# audio_switch.net
KiCad netlist of a schematic drawn in EAGLE
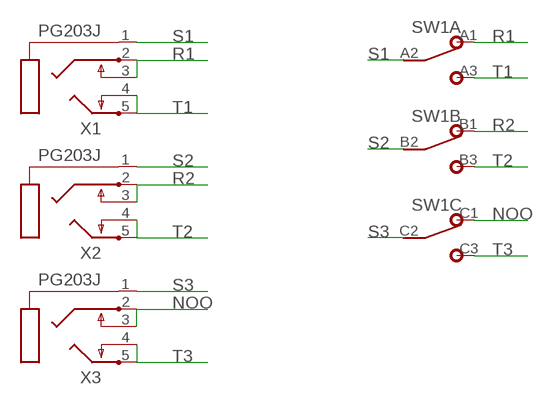
[diagram p0: schematic, sheet 1]

(export (version "E")
  (design (tool "Eeschema 10.0.6"))
  (components
    (comp (ref "SW1")
      (value "3PDT")
      (footprint "eagle-import:3PDT")
      (libsource (lib "eagle-import") (part "3PDT"))
    )
    (comp (ref "X1")
      (value "PG203J")
      (footprint "eagle-import:PG203J")
      (libsource (lib "eagle-import") (part "PG203J"))
    )
    (comp (ref "X2")
      (value "PG203J")
      (footprint "eagle-import:PG203J")
      (libsource (lib "eagle-import") (part "PG203J"))
    )
    (comp (ref "X3")
      (value "PG203J")
      (footprint "eagle-import:PG203J")
      (libsource (lib "eagle-import") (part "PG203J"))
    )
  )
  (nets
    (net (code "1") (name "/NOO") (class "Default")
      (node (ref "SW1") (pin "C1") (pinfunction "1_C1") (pintype "passive"))
      (node (ref "X3") (pin "2") (pinfunction "2_2") (pintype "passive"))
      (node (ref "X3") (pin "3") (pinfunction "3_3") (pintype "passive"))
    )
    (net (code "2") (name "/R1") (class "Default")
      (node (ref "SW1") (pin "A1") (pinfunction "1_A1") (pintype "passive"))
      (node (ref "X1") (pin "2") (pinfunction "2_2") (pintype "passive"))
      (node (ref "X1") (pin "3") (pinfunction "3_3") (pintype "passive"))
    )
    (net (code "3") (name "/R2") (class "Default")
      (node (ref "SW1") (pin "B1") (pinfunction "1_B1") (pintype "passive"))
      (node (ref "X2") (pin "2") (pinfunction "2_2") (pintype "passive"))
      (node (ref "X2") (pin "3") (pinfunction "3_3") (pintype "passive"))
    )
    (net (code "4") (name "/S1") (class "Default")
      (node (ref "SW1") (pin "A2") (pinfunction "2_A2") (pintype "passive"))
      (node (ref "X1") (pin "1") (pinfunction "1_1") (pintype "passive"))
    )
    (net (code "5") (name "/S2") (class "Default")
      (node (ref "SW1") (pin "B2") (pinfunction "2_B2") (pintype "passive"))
      (node (ref "X2") (pin "1") (pinfunction "1_1") (pintype "passive"))
    )
    (net (code "6") (name "/S3") (class "Default")
      (node (ref "SW1") (pin "C2") (pinfunction "2_C2") (pintype "passive"))
      (node (ref "X3") (pin "1") (pinfunction "1_1") (pintype "passive"))
    )
    (net (code "7") (name "/T1") (class "Default")
      (node (ref "SW1") (pin "A3") (pinfunction "3_A3") (pintype "passive"))
      (node (ref "X1") (pin "4") (pinfunction "4_4") (pintype "passive"))
      (node (ref "X1") (pin "5") (pinfunction "5_5") (pintype "passive"))
    )
    (net (code "8") (name "/T2") (class "Default")
      (node (ref "SW1") (pin "B3") (pinfunction "3_B3") (pintype "passive"))
      (node (ref "X2") (pin "4") (pinfunction "4_4") (pintype "passive"))
      (node (ref "X2") (pin "5") (pinfunction "5_5") (pintype "passive"))
    )
    (net (code "9") (name "/T3") (class "Default")
      (node (ref "SW1") (pin "C3") (pinfunction "3_C3") (pintype "passive"))
      (node (ref "X3") (pin "4") (pinfunction "4_4") (pintype "passive"))
      (node (ref "X3") (pin "5") (pinfunction "5_5") (pintype "passive"))
    )
  )
)
